# microSD.net
KiCad netlist of a schematic drawn in Altium Designer
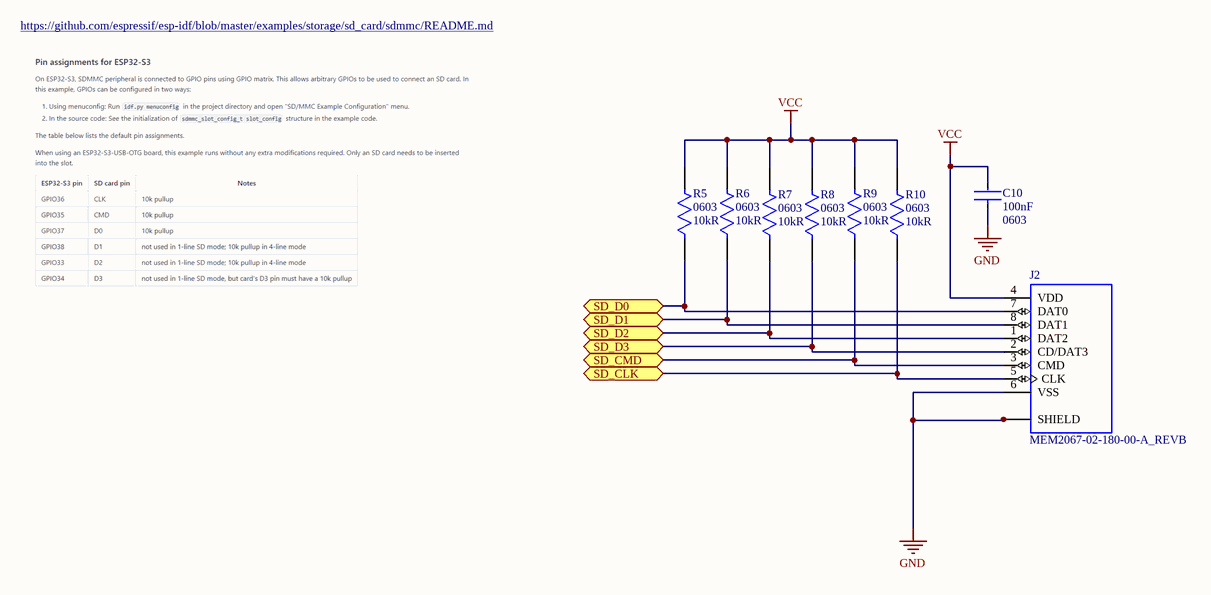
[diagram p0: microSD.SchDoc]

(export (version "E")
  (design (tool "Eeschema 10.0.6"))
  (components
    (comp (ref "C10")
      (value "CL10B104KB8WPNC")
      (footprint "FP-CL10-IPC_A")
      (description "Cap Ceramic 100nF 50V X7R ±10% Pad SMD 0603 +125°C T/R")
      (fields
        (field (name "CAPACITANCE") "100nF")
        (field (name "CASE/PACKAGE") "0603")
        (field (name "TOLERANCE") "10%")
      )
      (libsource (lib "Altium Content Vault") (part "b4654b650e69147ec39a6b967a45e02"))
    )
    (comp (ref "J2")
      (value "MEM2067-02-180-00-A_REVB")
      (footprint "WiCAN_lib:GCT_MEM2067-02-180-00-A_REVB")
      (description "Micro SD Memory Card ConnectorSMT, Hinged, 1.80mm Profile")
      (libsource (lib "WiCAN_lib") (part "MEM2067-02-180-00-A_REVB"))
    )
    (comp (ref "R5")
      (value "RMCF0603JG10K0")
      (footprint "FP-RMCF0603-MFG")
      (description "10kΩ ±5% 0.1W 0603 Thick Film Chip Resistor AEC-Q200 compliant")
      (fields
        (field (name "TOLERANCE") "5%")
        (field (name "CASE CODE (IMPERIAL)") "0603")
        (field (name "RESISTANCE") "10kR")
      )
      (libsource (lib "Altium Content Vault") (part "1029c3af85768c4190bb7ad29bc67b5"))
    )
    (comp (ref "R6")
      (value "RMCF0603JG10K0")
      (footprint "FP-RMCF0603-MFG")
      (description "10kΩ ±5% 0.1W 0603 Thick Film Chip Resistor AEC-Q200 compliant")
      (fields
        (field (name "TOLERANCE") "5%")
        (field (name "CASE CODE (IMPERIAL)") "0603")
        (field (name "RESISTANCE") "10kR")
      )
      (libsource (lib "Altium Content Vault") (part "1029c3af85768c4190bb7ad29bc67b5"))
    )
    (comp (ref "R7")
      (value "RMCF0603JG10K0")
      (footprint "FP-RMCF0603-MFG")
      (description "10kΩ ±5% 0.1W 0603 Thick Film Chip Resistor AEC-Q200 compliant")
      (fields
        (field (name "TOLERANCE") "5%")
        (field (name "CASE CODE (IMPERIAL)") "0603")
        (field (name "RESISTANCE") "10kR")
      )
      (libsource (lib "Altium Content Vault") (part "1029c3af85768c4190bb7ad29bc67b5"))
    )
    (comp (ref "R8")
      (value "RMCF0603JG10K0")
      (footprint "FP-RMCF0603-MFG")
      (description "10kΩ ±5% 0.1W 0603 Thick Film Chip Resistor AEC-Q200 compliant")
      (fields
        (field (name "TOLERANCE") "5%")
        (field (name "CASE CODE (IMPERIAL)") "0603")
        (field (name "RESISTANCE") "10kR")
      )
      (libsource (lib "Altium Content Vault") (part "1029c3af85768c4190bb7ad29bc67b5"))
    )
    (comp (ref "R9")
      (value "RMCF0603JG10K0")
      (footprint "FP-RMCF0603-MFG")
      (description "10kΩ ±5% 0.1W 0603 Thick Film Chip Resistor AEC-Q200 compliant")
      (fields
        (field (name "TOLERANCE") "5%")
        (field (name "CASE CODE (IMPERIAL)") "0603")
        (field (name "RESISTANCE") "10kR")
      )
      (libsource (lib "Altium Content Vault") (part "1029c3af85768c4190bb7ad29bc67b5"))
    )
    (comp (ref "R10")
      (value "RMCF0603JG10K0")
      (footprint "FP-RMCF0603-MFG")
      (description "10kΩ ±5% 0.1W 0603 Thick Film Chip Resistor AEC-Q200 compliant")
      (fields
        (field (name "TOLERANCE") "5%")
        (field (name "CASE CODE (IMPERIAL)") "0603")
        (field (name "RESISTANCE") "10kR")
      )
      (libsource (lib "Altium Content Vault") (part "1029c3af85768c4190bb7ad29bc67b5"))
    )
  )
  (nets
    (net (code "1") (name "/SD_CLK") (class "Default")
      (node (ref "J2") (pin "5") (pinfunction "CLK_5") (pintype "bidirectional"))
      (node (ref "R10") (pin "1") (pinfunction "1_1") (pintype "passive"))
    )
    (net (code "2") (name "/SD_CMD") (class "Default")
      (node (ref "J2") (pin "3") (pinfunction "CMD_3") (pintype "bidirectional"))
      (node (ref "R9") (pin "1") (pinfunction "1_1") (pintype "passive"))
    )
    (net (code "3") (name "/SD_D0") (class "Default")
      (node (ref "J2") (pin "7") (pinfunction "DAT0_7") (pintype "bidirectional"))
      (node (ref "R5") (pin "1") (pinfunction "1_1") (pintype "passive"))
    )
    (net (code "4") (name "/SD_D1") (class "Default")
      (node (ref "J2") (pin "8") (pinfunction "DAT1_8") (pintype "bidirectional"))
      (node (ref "R6") (pin "1") (pinfunction "1_1") (pintype "passive"))
    )
    (net (code "5") (name "/SD_D2") (class "Default")
      (node (ref "J2") (pin "1") (pinfunction "DAT2_1") (pintype "bidirectional"))
      (node (ref "R7") (pin "1") (pinfunction "1_1") (pintype "passive"))
    )
    (net (code "6") (name "/SD_D3") (class "Default")
      (node (ref "J2") (pin "2") (pinfunction "CD/DAT3_2") (pintype "bidirectional"))
      (node (ref "R8") (pin "1") (pinfunction "1_1") (pintype "passive"))
    )
    (net (code "7") (name "GND") (class "Default")
      (node (ref "C10") (pin "1") (pinfunction "1_1") (pintype "passive"))
      (node (ref "J2") (pin "10") (pinfunction "SHIELD_10") (pintype "passive"))
      (node (ref "J2") (pin "11") (pinfunction "SHIELD_11") (pintype "passive"))
      (node (ref "J2") (pin "12") (pinfunction "SHIELD_12") (pintype "passive"))
      (node (ref "J2") (pin "6") (pinfunction "VSS_6") (pintype "power_in"))
      (node (ref "J2") (pin "9") (pinfunction "SHIELD_9") (pintype "passive"))
    )
    (net (code "8") (name "VCC") (class "Default")
      (node (ref "C10") (pin "2") (pinfunction "2_2") (pintype "passive"))
      (node (ref "J2") (pin "4") (pinfunction "VDD_4") (pintype "passive"))
      (node (ref "R10") (pin "2") (pinfunction "2_2") (pintype "passive"))
      (node (ref "R5") (pin "2") (pinfunction "2_2") (pintype "passive"))
      (node (ref "R6") (pin "2") (pinfunction "2_2") (pintype "passive"))
      (node (ref "R7") (pin "2") (pinfunction "2_2") (pintype "passive"))
      (node (ref "R8") (pin "2") (pinfunction "2_2") (pintype "passive"))
      (node (ref "R9") (pin "2") (pinfunction "2_2") (pintype "passive"))
    )
  )
)
